# CARTE_E-STOP.net
KiCad netlist of a schematic drawn in EAGLE
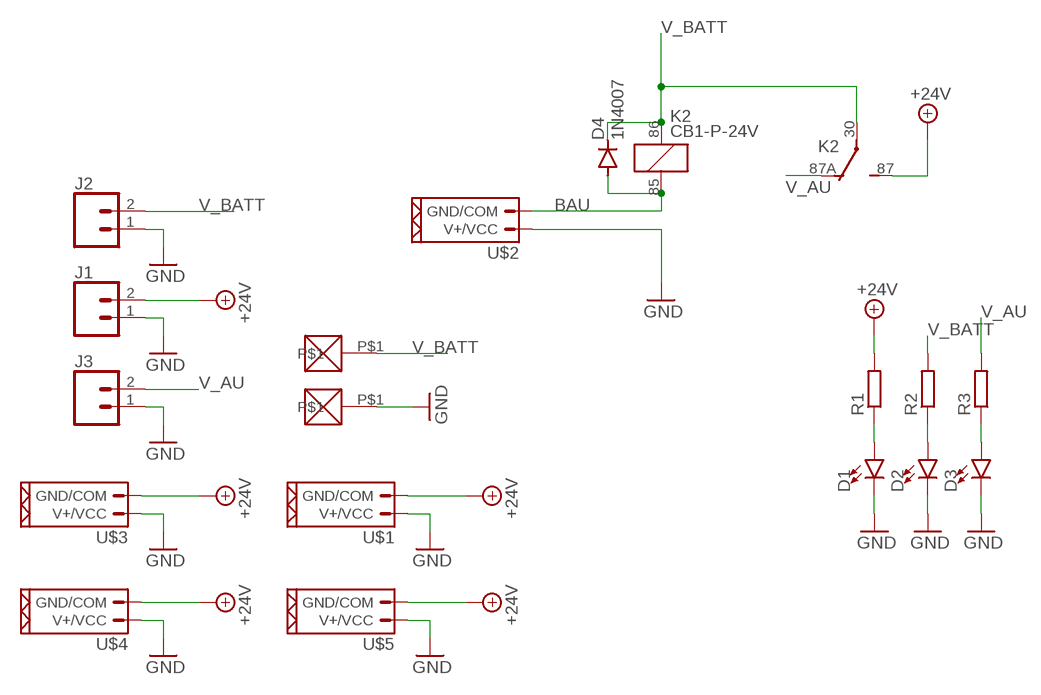
[diagram p0: schematic, sheet 1]

(export (version "E")
  (design (tool "Eeschema 10.0.6"))
  (components
    (comp (ref "D1")
      (value "LED3MM")
      (footprint "eagle-import:LED_3MM")
      (libsource (lib "eagle-import") (part "LED3MM"))
    )
    (comp (ref "D2")
      (value "LED3MM")
      (footprint "eagle-import:LED_3MM")
      (libsource (lib "eagle-import") (part "LED3MM"))
    )
    (comp (ref "D3")
      (value "LED3MM")
      (footprint "eagle-import:LED_3MM")
      (libsource (lib "eagle-import") (part "LED3MM"))
    )
    (comp (ref "D4")
      (value "1N4007")
      (footprint "eagle-import:DO41-10")
      (libsource (lib "eagle-import") (part "1N4004"))
    )
    (comp (ref "GND_BATT")
      (value "BAT_WIRE_SOLD")
      (footprint "eagle-import:LARGE_PAD_BATT")
      (libsource (lib "eagle-import") (part "BAT_WIRE_SOLD"))
    )
    (comp (ref "J1")
      (value "CONN_02POLAR")
      (footprint "eagle-import:MOLEX-1X2")
      (libsource (lib "eagle-import") (part "CONN_02POLAR"))
    )
    (comp (ref "J2")
      (value "CONN_02POLAR")
      (footprint "eagle-import:MOLEX-1X2")
      (libsource (lib "eagle-import") (part "CONN_02POLAR"))
    )
    (comp (ref "J3")
      (value "CONN_02POLAR")
      (footprint "eagle-import:MOLEX-1X2")
      (libsource (lib "eagle-import") (part "CONN_02POLAR"))
    )
    (comp (ref "K2")
      (value "CB1-P-24V")
      (footprint "eagle-import:CB1")
      (fields (field (name "MF") "AROMAT/ MATSUSHITA"))
      (libsource (lib "eagle-import") (part "CB1-P-24V"))
    )
    (comp (ref "R1")
      (value "R-EU_0207/2V")
      (footprint "eagle-import:0207_2V")
      (libsource (lib "eagle-import") (part "R-EU_0207/2V"))
    )
    (comp (ref "R2")
      (value "R-EU_0207/2V")
      (footprint "eagle-import:0207_2V")
      (libsource (lib "eagle-import") (part "R-EU_0207/2V"))
    )
    (comp (ref "R3")
      (value "R-EU_0207/2V")
      (footprint "eagle-import:0207_2V")
      (libsource (lib "eagle-import") (part "R-EU_0207/2V"))
    )
    (comp (ref "U$1")
      (value "CONN_02_PUI")
      (footprint "eagle-import:NSK396-2C")
      (libsource (lib "eagle-import") (part "CONN_02_PUI"))
    )
    (comp (ref "U$2")
      (value "CONN_02_PUI")
      (footprint "eagle-import:NSK396-2C")
      (libsource (lib "eagle-import") (part "CONN_02_PUI"))
    )
    (comp (ref "U$3")
      (value "CONN_02_PUI")
      (footprint "eagle-import:NSK396-2C")
      (libsource (lib "eagle-import") (part "CONN_02_PUI"))
    )
    (comp (ref "U$4")
      (value "CONN_02_PUI")
      (footprint "eagle-import:NSK396-2C")
      (libsource (lib "eagle-import") (part "CONN_02_PUI"))
    )
    (comp (ref "U$5")
      (value "CONN_02_PUI")
      (footprint "eagle-import:NSK396-2C")
      (libsource (lib "eagle-import") (part "CONN_02_PUI"))
    )
    (comp (ref "V+BATT")
      (value "BAT_WIRE_SOLD")
      (footprint "eagle-import:LARGE_PAD_BATT")
      (libsource (lib "eagle-import") (part "BAT_WIRE_SOLD"))
    )
  )
  (nets
    (net (code "1") (name "+24V") (class "Default")
      (node (ref "J1") (pin "2") (pinfunction "2_2") (pintype "passive"))
      (node (ref "K2") (pin "87") (pinfunction "S_87") (pintype "passive"))
      (node (ref "R1") (pin "2") (pinfunction "2_2") (pintype "passive"))
      (node (ref "U$1") (pin "P$1") (pinfunction "GND/COM_P$1") (pintype "passive"))
      (node (ref "U$3") (pin "P$1") (pinfunction "GND/COM_P$1") (pintype "passive"))
      (node (ref "U$4") (pin "P$1") (pinfunction "GND/COM_P$1") (pintype "passive"))
      (node (ref "U$5") (pin "P$1") (pinfunction "GND/COM_P$1") (pintype "passive"))
    )
    (net (code "2") (name "/BAU") (class "Default")
      (node (ref "D4") (pin "A") (pinfunction "A_A") (pintype "passive"))
      (node (ref "K2") (pin "85") (pinfunction "2_85") (pintype "passive"))
      (node (ref "U$2") (pin "P$1") (pinfunction "GND/COM_P$1") (pintype "passive"))
    )
    (net (code "3") (name "/V_AU") (class "Default")
      (node (ref "J3") (pin "2") (pinfunction "2_2") (pintype "passive"))
      (node (ref "K2") (pin "87A") (pinfunction "O_87A") (pintype "passive"))
      (node (ref "R3") (pin "2") (pinfunction "2_2") (pintype "passive"))
    )
    (net (code "4") (name "/V_BATT") (class "Default")
      (node (ref "D4") (pin "C") (pinfunction "C_C") (pintype "passive"))
      (node (ref "J2") (pin "2") (pinfunction "2_2") (pintype "passive"))
      (node (ref "K2") (pin "30") (pinfunction "P_30") (pintype "passive"))
      (node (ref "K2") (pin "86") (pinfunction "1_86") (pintype "passive"))
      (node (ref "R2") (pin "2") (pinfunction "2_2") (pintype "passive"))
      (node (ref "V+BATT") (pin "P$1") (pinfunction "P$1_P$1") (pintype "bidirectional"))
    )
    (net (code "5") (name "GND") (class "Default")
      (node (ref "D1") (pin "K") (pinfunction "C_K") (pintype "passive"))
      (node (ref "D2") (pin "K") (pinfunction "C_K") (pintype "passive"))
      (node (ref "D3") (pin "K") (pinfunction "C_K") (pintype "passive"))
      (node (ref "GND_BATT") (pin "P$1") (pinfunction "P$1_P$1") (pintype "bidirectional"))
      (node (ref "J1") (pin "1") (pinfunction "1_1") (pintype "passive"))
      (node (ref "J2") (pin "1") (pinfunction "1_1") (pintype "passive"))
      (node (ref "J3") (pin "1") (pinfunction "1_1") (pintype "passive"))
      (node (ref "U$1") (pin "P$2") (pinfunction "V+/VCC_P$2") (pintype "passive"))
      (node (ref "U$2") (pin "P$2") (pinfunction "V+/VCC_P$2") (pintype "passive"))
      (node (ref "U$3") (pin "P$2") (pinfunction "V+/VCC_P$2") (pintype "passive"))
      (node (ref "U$4") (pin "P$2") (pinfunction "V+/VCC_P$2") (pintype "passive"))
      (node (ref "U$5") (pin "P$2") (pinfunction "V+/VCC_P$2") (pintype "passive"))
    )
    (net (code "6") (name "Net-(D1-PadA)") (class "Default")
      (node (ref "D1") (pin "A") (pinfunction "A_A") (pintype "passive"))
      (node (ref "R1") (pin "1") (pinfunction "1_1") (pintype "passive"))
    )
    (net (code "7") (name "Net-(D2-PadA)") (class "Default")
      (node (ref "D2") (pin "A") (pinfunction "A_A") (pintype "passive"))
      (node (ref "R2") (pin "1") (pinfunction "1_1") (pintype "passive"))
    )
    (net (code "8") (name "Net-(D3-PadA)") (class "Default")
      (node (ref "D3") (pin "A") (pinfunction "A_A") (pintype "passive"))
      (node (ref "R3") (pin "1") (pinfunction "1_1") (pintype "passive"))
    )
  )
)
